# discriminator.net
KiCad netlist of a schematic drawn in EAGLE
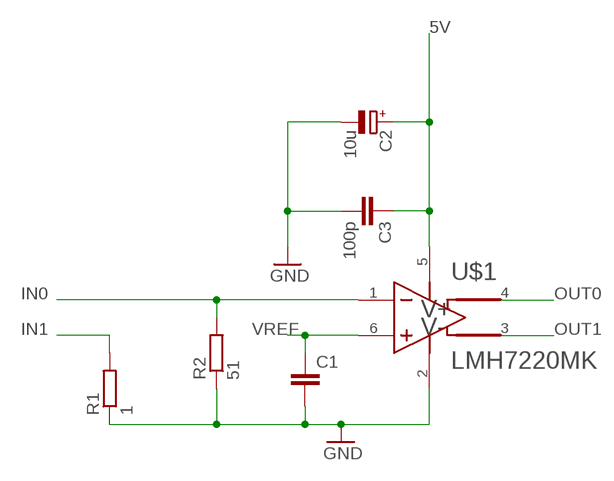
[diagram p0: schematic, sheet 1]

(export (version "E")
  (design (tool "Eeschema 10.0.6"))
  (components
    (comp (ref "C1")
      (value "C-EUC2012")
      (footprint "eagle-import:C2012")
      (libsource (lib "eagle-import") (part "C-EUC2012"))
    )
    (comp (ref "C2")
      (value "10u")
      (footprint "eagle-import:CT3528")
      (libsource (lib "eagle-import") (part "CPOL-EUCT3528"))
    )
    (comp (ref "C3")
      (value "100p")
      (footprint "eagle-import:C2012")
      (libsource (lib "eagle-import") (part "C-EUC2012"))
    )
    (comp (ref "R1")
      (value "1")
      (footprint "eagle-import:R0805")
      (libsource (lib "eagle-import") (part "R-EU_R0805"))
    )
    (comp (ref "R2")
      (value "51")
      (footprint "eagle-import:R0805")
      (libsource (lib "eagle-import") (part "R-EU_R0805"))
    )
    (comp (ref "U$1")
      (value "LMH7220MK")
      (footprint "eagle-import:TSOP-6.PAC")
      (libsource (lib "eagle-import") (part "LMH7220MK"))
    )
  )
  (nets
    (net (code "1") (name "/5V") (class "Default")
      (node (ref "C2") (pin "+") (pinfunction "+_+") (pintype "passive"))
      (node (ref "C3") (pin "1") (pinfunction "1_1") (pintype "passive"))
      (node (ref "U$1") (pin "5") (pinfunction "V+_5") (pintype "power_in"))
    )
    (net (code "2") (name "/IN0") (class "Default")
      (node (ref "R2") (pin "2") (pinfunction "2_2") (pintype "passive"))
      (node (ref "U$1") (pin "1") (pinfunction "-IN_1") (pintype "input"))
    )
    (net (code "3") (name "/IN1") (class "Default")
      (node (ref "R1") (pin "2") (pinfunction "2_2") (pintype "passive"))
    )
    (net (code "4") (name "/OUT0") (class "Default")
      (node (ref "U$1") (pin "4") (pinfunction "+OUT_4") (pintype "input"))
    )
    (net (code "5") (name "/OUT1") (class "Default")
      (node (ref "U$1") (pin "3") (pinfunction "-OUT_3") (pintype "output"))
    )
    (net (code "6") (name "/VREF") (class "Default")
      (node (ref "C1") (pin "1") (pinfunction "1_1") (pintype "passive"))
      (node (ref "U$1") (pin "6") (pinfunction "+IN_6") (pintype "output"))
    )
    (net (code "7") (name "GND") (class "Default")
      (node (ref "C1") (pin "2") (pinfunction "2_2") (pintype "passive"))
      (node (ref "C2") (pin "-") (pinfunction "-_-") (pintype "passive"))
      (node (ref "C3") (pin "2") (pinfunction "2_2") (pintype "passive"))
      (node (ref "R1") (pin "1") (pinfunction "1_1") (pintype "passive"))
      (node (ref "R2") (pin "1") (pinfunction "1_1") (pintype "passive"))
      (node (ref "U$1") (pin "2") (pinfunction "V-_2") (pintype "power_in"))
    )
  )
)
